# voltagesource.net
KiCad netlist of a schematic drawn in Altium Designer
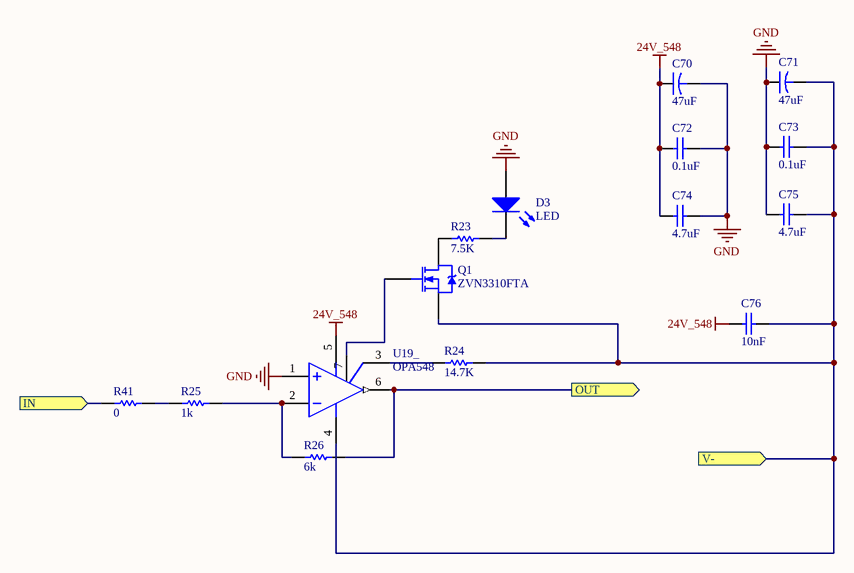
[diagram p0: voltagesource.SchDoc]

(export (version "E")
  (design (tool "Eeschema 10.0.6"))
  (components
    (comp (ref "C70")
      (value "47uF")
      (footprint "bigcap")
      (description "Capacitor, 47uF NICHICON")
      (libsource (lib "Arturo_Approved") (part "UCY2C470MPD"))
    )
    (comp (ref "C71")
      (value "47uF")
      (footprint "bigcap")
      (description "Capacitor, 47uF NICHICON")
      (libsource (lib "Arturo_Approved") (part "UCY2C470MPD"))
    )
    (comp (ref "C72")
      (value "0.1uF")
      (footprint "0402_Cap")
      (description "Capacitor, 0.1uF, 0805")
      (libsource (lib "Arturo_Approved") (part "CL21B104KACNNNC"))
    )
    (comp (ref "C73")
      (value "0.1uF")
      (footprint "0402_Cap")
      (description "Capacitor, 0.1uF, 0805")
      (libsource (lib "Arturo_Approved") (part "CL21B104KACNNNC"))
    )
    (comp (ref "C74")
      (value "4.7uF")
      (footprint "0402_Cap")
      (description "Capacitor, 4.7uF, 0805")
      (libsource (lib "Arturo_Approved") (part "CL21A475KAQNNNE"))
    )
    (comp (ref "C75")
      (value "4.7uF")
      (footprint "0402_Cap")
      (description "Capacitor, 4.7uF, 0805")
      (libsource (lib "Arturo_Approved") (part "CL21A475KAQNNNE"))
    )
    (comp (ref "C76")
      (value "10nF")
      (footprint "0402_Cap")
      (description "Capacitor, 10nF, 0805")
      (libsource (lib "Arturo_Approved") (part "C0805C103K1RAC7210"))
    )
    (comp (ref "D3")
      (value "LED")
      (footprint "STD_LED")
      (description "Typical LED")
      (libsource (lib "Arturo_Approved") (part "LNJ037X8ARA"))
    )
    (comp (ref "Q1")
      (value "ZVN3310FTA")
      (footprint "SOT-23B_M")
      (description "N-Channel Power MOSFET")
      (libsource (lib "Arturo_Approved") (part "ZVN3310FTA"))
    )
    (comp (ref "R23")
      (value "7.5K")
      (footprint "0402_Res")
      (description "7.5K 1% 1/4W")
      (libsource (lib "Arturo_Approved") (part "ERJ-PB6D7501V"))
    )
    (comp (ref "R24")
      (value "14.7K")
      (footprint "0402_Res")
      (description "14.7K 1% 1/4W")
      (libsource (lib "Arturo_Approved") (part "RC0805FR-0714K7L"))
    )
    (comp (ref "R25")
      (value "1k")
      (footprint "0402_Res")
      (description "1K 1% 1/4W")
      (libsource (lib "Arturo_Approved") (part "RNCP0805FTD1K00"))
    )
    (comp (ref "R26")
      (value "6k")
      (footprint "0402_Res")
      (description "6K 1% 1/4W")
      (libsource (lib "Arturo_Approved") (part "RMCF0805FT5K60"))
    )
    (comp (ref "R41")
      (value "0")
      (footprint "0402_Res")
      (description "0 ohm jumper")
      (libsource (lib "Arturo_Approved") (part "RMCF0805ZT0R00"))
    )
    (comp (ref "U19_")
      (value "OPA548")
      (footprint "TO-220-7")
      (description "High power op amp")
      (libsource (lib "Arturo_Approved") (part "OPA548T"))
    )
  )
  (nets
    (net (code "1") (name "/IN") (class "Default")
      (node (ref "R41") (pin "1") (pinfunction "1_1") (pintype "passive"))
    )
    (net (code "2") (name "/OUT") (class "Default")
      (node (ref "R26") (pin "2") (pinfunction "2_2") (pintype "passive"))
      (node (ref "U19_") (pin "6") (pinfunction "OUT_6") (pintype "output"))
    )
    (net (code "3") (name "/V-") (class "Default")
      (node (ref "C71") (pin "2") (pinfunction "2_2") (pintype "passive"))
      (node (ref "C73") (pin "2") (pinfunction "2_2") (pintype "passive"))
      (node (ref "C75") (pin "2") (pinfunction "2_2") (pintype "passive"))
      (node (ref "C76") (pin "2") (pinfunction "2_2") (pintype "passive"))
      (node (ref "Q1") (pin "3") (pinfunction "S_3") (pintype "passive"))
      (node (ref "R24") (pin "2") (pinfunction "2_2") (pintype "passive"))
      (node (ref "U19_") (pin "4") (pinfunction "V-_4") (pintype "power_in"))
    )
    (net (code "4") (name "24V_548") (class "Default")
      (node (ref "C70") (pin "1") (pinfunction "1_1") (pintype "passive"))
      (node (ref "C72") (pin "1") (pinfunction "1_1") (pintype "passive"))
      (node (ref "C74") (pin "1") (pinfunction "1_1") (pintype "passive"))
      (node (ref "C76") (pin "1") (pinfunction "1_1") (pintype "passive"))
      (node (ref "U19_") (pin "5") (pinfunction "V+_5") (pintype "power_in"))
    )
    (net (code "5") (name "GND") (class "Default")
      (node (ref "C70") (pin "2") (pinfunction "2_2") (pintype "passive"))
      (node (ref "C71") (pin "1") (pinfunction "1_1") (pintype "passive"))
      (node (ref "C72") (pin "2") (pinfunction "2_2") (pintype "passive"))
      (node (ref "C73") (pin "1") (pinfunction "1_1") (pintype "passive"))
      (node (ref "C74") (pin "2") (pinfunction "2_2") (pintype "passive"))
      (node (ref "C75") (pin "1") (pinfunction "1_1") (pintype "passive"))
      (node (ref "D3") (pin "1") (pinfunction "1_1") (pintype "passive"))
      (node (ref "U19_") (pin "1") (pinfunction "IN-_1") (pintype "passive"))
    )
    (net (code "6") (name "Net-(D3-Pad2)") (class "Default")
      (node (ref "D3") (pin "2") (pinfunction "2_2") (pintype "passive"))
      (node (ref "R23") (pin "2") (pinfunction "2_2") (pintype "passive"))
    )
    (net (code "7") (name "Net-(Q1-D)") (class "Default")
      (node (ref "Q1") (pin "2") (pinfunction "D_2") (pintype "passive"))
      (node (ref "R23") (pin "1") (pinfunction "1_1") (pintype "passive"))
    )
    (net (code "8") (name "Net-(Q1-G)") (class "Default")
      (node (ref "Q1") (pin "1") (pinfunction "G_1") (pintype "passive"))
      (node (ref "U19_") (pin "7") (pinfunction "OS_NUL_7") (pintype "passive"))
    )
    (net (code "9") (name "Net-(R25-Pad1)") (class "Default")
      (node (ref "R25") (pin "1") (pinfunction "1_1") (pintype "passive"))
      (node (ref "R41") (pin "2") (pinfunction "2_2") (pintype "passive"))
    )
    (net (code "10") (name "Net-(U19_-IN+)") (class "Default")
      (node (ref "R25") (pin "2") (pinfunction "2_2") (pintype "passive"))
      (node (ref "R26") (pin "1") (pinfunction "1_1") (pintype "passive"))
      (node (ref "U19_") (pin "2") (pinfunction "IN+_2") (pintype "passive"))
    )
    (net (code "11") (name "Net-(U19_-TAB)") (class "Default")
      (node (ref "R24") (pin "1") (pinfunction "1_1") (pintype "passive"))
      (node (ref "U19_") (pin "3") (pinfunction "TAB_3") (pintype "passive"))
    )
  )
)
